# ICAN-7006-AiUi.net
KiCad netlist of a schematic drawn in Altium Designer
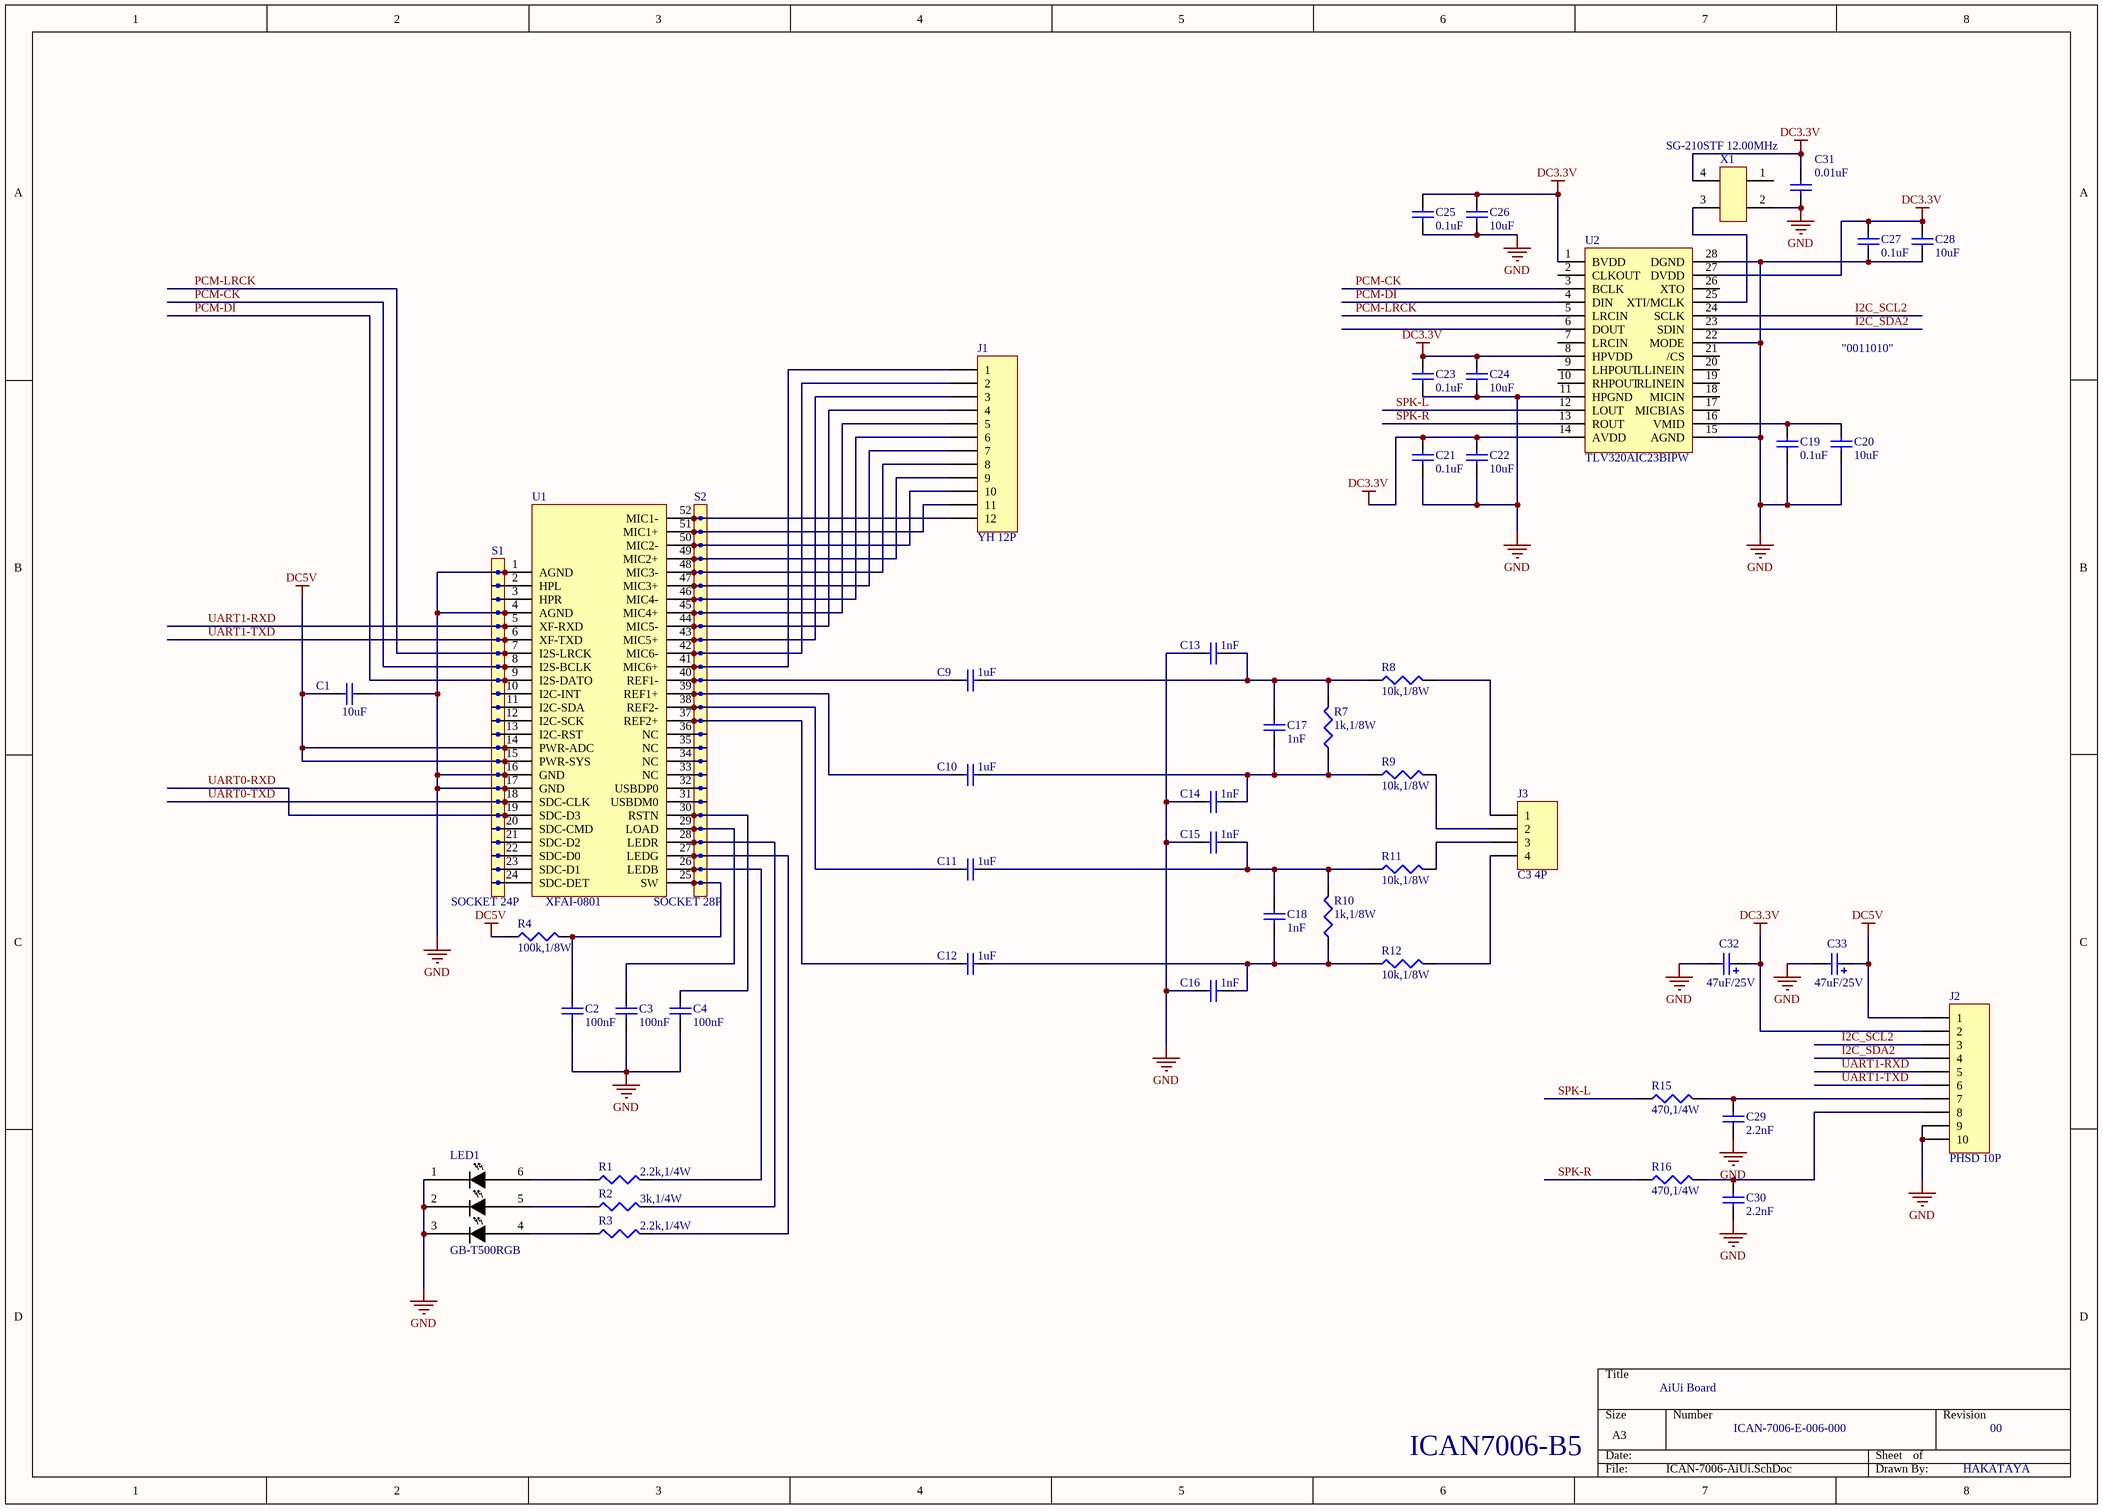
[diagram p0: ICAN-7006-AiUi.SchDoc]

(export (version "E")
  (design (tool "Eeschema 10.0.6"))
  (components
    (comp (ref "C1")
      (value "10uF")
      (footprint "[0805]2012")
      (description "Capacitor")
      (fields (field (name "PUBLISHER") "Altium Limited"))
      (libsource (lib "Miscellaneous Devices") (part "Cap Semi"))
    )
    (comp (ref "C2")
      (value "100nF")
      (footprint "[0805]2012")
      (description "Capacitor")
      (fields (field (name "PUBLISHER") "Altium Limited"))
      (libsource (lib "Miscellaneous Devices") (part "Cap Semi"))
    )
    (comp (ref "C3")
      (value "100nF")
      (footprint "[0805]2012")
      (description "Capacitor")
      (fields (field (name "PUBLISHER") "Altium Limited"))
      (libsource (lib "Miscellaneous Devices") (part "Cap Semi"))
    )
    (comp (ref "C4")
      (value "100nF")
      (footprint "[0805]2012")
      (description "Capacitor")
      (fields (field (name "PUBLISHER") "Altium Limited"))
      (libsource (lib "Miscellaneous Devices") (part "Cap Semi"))
    )
    (comp (ref "C9")
      (value "1uF")
      (footprint "[0805]2012")
      (description "Capacitor")
      (fields (field (name "PUBLISHER") "Altium Limited"))
      (libsource (lib "Miscellaneous Devices") (part "Cap Semi"))
    )
    (comp (ref "C10")
      (value "1uF")
      (footprint "[0805]2012")
      (description "Capacitor")
      (fields (field (name "PUBLISHER") "Altium Limited"))
      (libsource (lib "Miscellaneous Devices") (part "Cap Semi"))
    )
    (comp (ref "C11")
      (value "1uF")
      (footprint "[0805]2012")
      (description "Capacitor")
      (fields (field (name "PUBLISHER") "Altium Limited"))
      (libsource (lib "Miscellaneous Devices") (part "Cap Semi"))
    )
    (comp (ref "C12")
      (value "1uF")
      (footprint "[0805]2012")
      (description "Capacitor")
      (fields (field (name "PUBLISHER") "Altium Limited"))
      (libsource (lib "Miscellaneous Devices") (part "Cap Semi"))
    )
    (comp (ref "C13")
      (value "1nF")
      (footprint "[0805]2012")
      (description "Capacitor")
      (fields (field (name "PUBLISHER") "Altium Limited"))
      (libsource (lib "Miscellaneous Devices") (part "Cap Semi"))
    )
    (comp (ref "C14")
      (value "1nF")
      (footprint "[0805]2012")
      (description "Capacitor")
      (fields (field (name "PUBLISHER") "Altium Limited"))
      (libsource (lib "Miscellaneous Devices") (part "Cap Semi"))
    )
    (comp (ref "C15")
      (value "1nF")
      (footprint "[0805]2012")
      (description "Capacitor")
      (fields (field (name "PUBLISHER") "Altium Limited"))
      (libsource (lib "Miscellaneous Devices") (part "Cap Semi"))
    )
    (comp (ref "C16")
      (value "1nF")
      (footprint "[0805]2012")
      (description "Capacitor")
      (fields (field (name "PUBLISHER") "Altium Limited"))
      (libsource (lib "Miscellaneous Devices") (part "Cap Semi"))
    )
    (comp (ref "C17")
      (value "1nF")
      (footprint "[0805]2012")
      (description "Capacitor")
      (fields (field (name "PUBLISHER") "Altium Limited"))
      (libsource (lib "Miscellaneous Devices") (part "Cap Semi"))
    )
    (comp (ref "C18")
      (value "1nF")
      (footprint "[0805]2012")
      (description "Capacitor")
      (fields (field (name "PUBLISHER") "Altium Limited"))
      (libsource (lib "Miscellaneous Devices") (part "Cap Semi"))
    )
    (comp (ref "C19")
      (value "0.1uF")
      (footprint "[0805]2012")
      (description "Capacitor")
      (fields (field (name "PUBLISHER") "Altium Limited"))
      (libsource (lib "Miscellaneous Devices") (part "Cap Semi"))
    )
    (comp (ref "C20")
      (value "10uF")
      (footprint "[0805]2012")
      (description "Capacitor")
      (fields (field (name "PUBLISHER") "Altium Limited"))
      (libsource (lib "Miscellaneous Devices") (part "Cap Semi"))
    )
    (comp (ref "C21")
      (value "0.1uF")
      (footprint "[0805]2012")
      (description "Capacitor")
      (fields (field (name "PUBLISHER") "Altium Limited"))
      (libsource (lib "Miscellaneous Devices") (part "Cap Semi"))
    )
    (comp (ref "C22")
      (value "10uF")
      (footprint "[0805]2012")
      (description "Capacitor")
      (fields (field (name "PUBLISHER") "Altium Limited"))
      (libsource (lib "Miscellaneous Devices") (part "Cap Semi"))
    )
    (comp (ref "C23")
      (value "0.1uF")
      (footprint "[0805]2012")
      (description "Capacitor")
      (fields (field (name "PUBLISHER") "Altium Limited"))
      (libsource (lib "Miscellaneous Devices") (part "Cap Semi"))
    )
    (comp (ref "C24")
      (value "10uF")
      (footprint "[0805]2012")
      (description "Capacitor")
      (fields (field (name "PUBLISHER") "Altium Limited"))
      (libsource (lib "Miscellaneous Devices") (part "Cap Semi"))
    )
    (comp (ref "C25")
      (value "0.1uF")
      (footprint "[0805]2012")
      (description "Capacitor")
      (fields (field (name "PUBLISHER") "Altium Limited"))
      (libsource (lib "Miscellaneous Devices") (part "Cap Semi"))
    )
    (comp (ref "C26")
      (value "10uF")
      (footprint "[0805]2012")
      (description "Capacitor")
      (fields (field (name "PUBLISHER") "Altium Limited"))
      (libsource (lib "Miscellaneous Devices") (part "Cap Semi"))
    )
    (comp (ref "C27")
      (value "0.1uF")
      (footprint "[0805]2012")
      (description "Capacitor")
      (fields (field (name "PUBLISHER") "Altium Limited"))
      (libsource (lib "Miscellaneous Devices") (part "Cap Semi"))
    )
    (comp (ref "C28")
      (value "10uF")
      (footprint "[0805]2012")
      (description "Capacitor")
      (fields (field (name "PUBLISHER") "Altium Limited"))
      (libsource (lib "Miscellaneous Devices") (part "Cap Semi"))
    )
    (comp (ref "C29")
      (value "2.2nF")
      (footprint "[0805]2012")
      (description "Capacitor")
      (fields (field (name "PUBLISHER") "Altium Limited"))
      (libsource (lib "Miscellaneous Devices") (part "Cap Semi"))
    )
    (comp (ref "C30")
      (value "2.2nF")
      (footprint "[0805]2012")
      (description "Capacitor")
      (fields (field (name "PUBLISHER") "Altium Limited"))
      (libsource (lib "Miscellaneous Devices") (part "Cap Semi"))
    )
    (comp (ref "C31")
      (value "0.01uF")
      (footprint "HAKATAYA:[0805]2012")
      (description "Capacitor (Semiconductor SIM Model)")
      (fields (field (name "PUBLISHER") "Altium Limited"))
      (libsource (lib "Miscellaneous Devices") (part "Cap Semi"))
    )
    (comp (ref "C32")
      (value "47uF/25V")
      (footprint "HAKATAYA:Capa MH5 PITCH2.5mm")
      (description "Polarized Capacitor (Axial)")
      (fields (field (name "PUBLISHER") "Altium Limited"))
      (libsource (lib "Miscellaneous Devices") (part "Cap Pol2"))
    )
    (comp (ref "C33")
      (value "47uF/25V")
      (footprint "HAKATAYA:Capa MH5 PITCH2.5mm")
      (description "Polarized Capacitor (Axial)")
      (fields (field (name "PUBLISHER") "Altium Limited"))
      (libsource (lib "Miscellaneous Devices") (part "Cap Pol2"))
    )
    (comp (ref "J1")
      (value "YH 12P")
      (footprint "HAKATAYA:HY-12AW")
      (description "Header, 12-Pin")
      (fields (field (name "PUBLISHER") "Altium Limited"))
      (libsource (lib "Miscellaneous Connectors") (part "Header 12"))
    )
    (comp (ref "J2")
      (value "PHSD 10P")
      (footprint "HAKATAYA:PHSD WV05x2")
      (description "Header, 10-Pin")
      (fields (field (name "PUBLISHER") "Altium Limited"))
      (libsource (lib "Miscellaneous Connectors") (part "Header 10"))
    )
    (comp (ref "J3")
      (value "C3 4P")
      (footprint "HAKATAYA:C3-S4")
      (description "Header, 4-Pin")
      (fields (field (name "PUBLISHER") "Altium Limited"))
      (libsource (lib "Miscellaneous Connectors") (part "Header 4"))
    )
    (comp (ref "LED1")
      (value "GB-T500RGB")
      (footprint "HAKATAYA:LED SMD RGB")
      (description "LED RGB")
      (libsource (lib "*") (part "LED Tri-COLOR"))
    )
    (comp (ref "R1")
      (value "2.2k,1/4W")
      (footprint "[0805]2012")
      (description "Resistor")
      (fields (field (name "PUBLISHER") "Altium Limited"))
      (libsource (lib "Miscellaneous Devices") (part "Res3"))
    )
    (comp (ref "R2")
      (value "3k,1/4W")
      (footprint "[0805]2012")
      (description "Resistor")
      (fields (field (name "PUBLISHER") "Altium Limited"))
      (libsource (lib "Miscellaneous Devices") (part "Res3"))
    )
    (comp (ref "R3")
      (value "2.2k,1/4W")
      (footprint "[0805]2012")
      (description "Resistor")
      (fields (field (name "PUBLISHER") "Altium Limited"))
      (libsource (lib "Miscellaneous Devices") (part "Res3"))
    )
    (comp (ref "R4")
      (value "100k,1/8W")
      (footprint "[0805]2012")
      (description "Resistor")
      (fields (field (name "PUBLISHER") "Altium Limited"))
      (libsource (lib "Miscellaneous Devices") (part "Res3"))
    )
    (comp (ref "R7")
      (value "1k,1/8W")
      (footprint "[0805]2012")
      (description "Resistor")
      (fields (field (name "PUBLISHER") "Altium Limited"))
      (libsource (lib "Miscellaneous Devices") (part "Res3"))
    )
    (comp (ref "R8")
      (value "10k,1/8W")
      (footprint "[0805]2012")
      (description "Resistor")
      (fields (field (name "PUBLISHER") "Altium Limited"))
      (libsource (lib "Miscellaneous Devices") (part "Res3"))
    )
    (comp (ref "R9")
      (value "10k,1/8W")
      (footprint "[0805]2012")
      (description "Resistor")
      (fields (field (name "PUBLISHER") "Altium Limited"))
      (libsource (lib "Miscellaneous Devices") (part "Res3"))
    )
    (comp (ref "R10")
      (value "1k,1/8W")
      (footprint "[0805]2012")
      (description "Resistor")
      (fields (field (name "PUBLISHER") "Altium Limited"))
      (libsource (lib "Miscellaneous Devices") (part "Res3"))
    )
    (comp (ref "R11")
      (value "10k,1/8W")
      (footprint "[0805]2012")
      (description "Resistor")
      (fields (field (name "PUBLISHER") "Altium Limited"))
      (libsource (lib "Miscellaneous Devices") (part "Res3"))
    )
    (comp (ref "R12")
      (value "10k,1/8W")
      (footprint "[0805]2012")
      (description "Resistor")
      (fields (field (name "PUBLISHER") "Altium Limited"))
      (libsource (lib "Miscellaneous Devices") (part "Res3"))
    )
    (comp (ref "R15")
      (value "470,1/4W")
      (footprint "[0805]2012")
      (description "Resistor")
      (fields (field (name "PUBLISHER") "Altium Limited"))
      (libsource (lib "Miscellaneous Devices") (part "Res3"))
    )
    (comp (ref "R16")
      (value "470,1/4W")
      (footprint "[0805]2012")
      (description "Resistor")
      (fields (field (name "PUBLISHER") "Altium Limited"))
      (libsource (lib "Miscellaneous Devices") (part "Res3"))
    )
    (comp (ref "S1")
      (value "SOCKET 24P")
      (footprint "HAKATAYA:CONN 2.0mm X 24")
      (description "IC SOCKET")
      (libsource (lib "*") (part "SOCKET 24P"))
    )
    (comp (ref "S2")
      (value "SOCKET 28P")
      (footprint "HAKATAYA:CONN 2.0mm X 28")
      (description "IC SOCKET")
      (libsource (lib "*") (part "SOCKET 28P"))
    )
    (comp (ref "U1")
      (value "XFAI-0801")
      (footprint "HAKATAYA:XFAI-0801")
      (description "AiUI")
      (libsource (lib "HAKATAYA") (part "XFAI-0801"))
    )
    (comp (ref "U2")
      (value "TLV320AIC23BIPW")
      (footprint "HAKATAYA:PW 28p")
      (description "DAC")
      (libsource (lib "HAKATAYA") (part "IC28"))
    )
    (comp (ref "X1")
      (value "SG-210STF 12.00MHz")
      (footprint "HAKATAYA:XTAL SPXO")
      (description "Crystal oscilator")
      (libsource (lib "HAKATAYA") (part "IC4"))
    )
  )
  (nets
    (net (code "1") (name "/I2C_SCL2") (class "Default")
      (node (ref "J2") (pin "3") (pinfunction "3_3") (pintype "passive"))
      (node (ref "U2") (pin "24") (pinfunction "SCLK_24") (pintype "passive"))
    )
    (net (code "2") (name "/I2C_SDA2") (class "Default")
      (node (ref "J2") (pin "4") (pinfunction "4_4") (pintype "passive"))
      (node (ref "U2") (pin "23") (pinfunction "SDIN_23") (pintype "passive"))
    )
    (net (code "3") (name "/PCM-CK") (class "Default")
      (node (ref "S1") (pin "8") (pinfunction "8_8") (pintype "passive"))
      (node (ref "U1") (pin "8") (pinfunction "I2S-BCLK_8") (pintype "passive"))
      (node (ref "U2") (pin "3") (pinfunction "BCLK_3") (pintype "passive"))
    )
    (net (code "4") (name "/PCM-DI") (class "Default")
      (node (ref "S1") (pin "9") (pinfunction "9_9") (pintype "passive"))
      (node (ref "U1") (pin "9") (pinfunction "I2S-DATO_9") (pintype "passive"))
      (node (ref "U2") (pin "4") (pinfunction "DIN_4") (pintype "passive"))
    )
    (net (code "5") (name "/PCM-LRCK") (class "Default")
      (node (ref "S1") (pin "7") (pinfunction "7_7") (pintype "passive"))
      (node (ref "U1") (pin "7") (pinfunction "I2S-LRCK_7") (pintype "passive"))
      (node (ref "U2") (pin "5") (pinfunction "LRCIN_5") (pintype "passive"))
    )
    (net (code "6") (name "/SPK-L") (class "Default")
      (node (ref "R15") (pin "1") (pinfunction "1_1") (pintype "passive"))
      (node (ref "U2") (pin "12") (pinfunction "LOUT_12") (pintype "passive"))
    )
    (net (code "7") (name "/SPK-R") (class "Default")
      (node (ref "R16") (pin "1") (pinfunction "1_1") (pintype "passive"))
      (node (ref "U2") (pin "13") (pinfunction "ROUT_13") (pintype "passive"))
    )
    (net (code "8") (name "/UART0-RXD") (class "Default")
      (node (ref "S1") (pin "19") (pinfunction "19_19") (pintype "passive"))
      (node (ref "U1") (pin "19") (pinfunction "SDC-D3_19") (pintype "passive"))
    )
    (net (code "9") (name "/UART0-TXD") (class "Default")
      (node (ref "S1") (pin "18") (pinfunction "18_18") (pintype "passive"))
      (node (ref "U1") (pin "18") (pinfunction "SDC-CLK_18") (pintype "passive"))
    )
    (net (code "10") (name "/UART1-RXD") (class "Default")
      (node (ref "J2") (pin "5") (pinfunction "5_5") (pintype "passive"))
      (node (ref "S1") (pin "5") (pinfunction "5_5") (pintype "passive"))
      (node (ref "U1") (pin "5") (pinfunction "XF-RXD_5") (pintype "passive"))
    )
    (net (code "11") (name "/UART1-TXD") (class "Default")
      (node (ref "J2") (pin "6") (pinfunction "6_6") (pintype "passive"))
      (node (ref "S1") (pin "6") (pinfunction "6_6") (pintype "passive"))
      (node (ref "U1") (pin "6") (pinfunction "XF-TXD_6") (pintype "passive"))
    )
    (net (code "12") (name "DC3.3V") (class "Default")
      (node (ref "C21") (pin "2") (pinfunction "2_2") (pintype "passive"))
      (node (ref "C22") (pin "2") (pinfunction "2_2") (pintype "passive"))
      (node (ref "C23") (pin "2") (pinfunction "2_2") (pintype "passive"))
      (node (ref "C24") (pin "2") (pinfunction "2_2") (pintype "passive"))
      (node (ref "C25") (pin "2") (pinfunction "2_2") (pintype "passive"))
      (node (ref "C26") (pin "2") (pinfunction "2_2") (pintype "passive"))
      (node (ref "C27") (pin "2") (pinfunction "2_2") (pintype "passive"))
      (node (ref "C28") (pin "2") (pinfunction "2_2") (pintype "passive"))
      (node (ref "C31") (pin "2") (pinfunction "2_2") (pintype "passive"))
      (node (ref "C32") (pin "1") (pinfunction "1_1") (pintype "passive"))
      (node (ref "J2") (pin "2") (pinfunction "2_2") (pintype "passive"))
      (node (ref "U2") (pin "1") (pinfunction "BVDD_1") (pintype "passive"))
      (node (ref "U2") (pin "14") (pinfunction "AVDD_14") (pintype "passive"))
      (node (ref "U2") (pin "27") (pinfunction "DVDD_27") (pintype "passive"))
      (node (ref "U2") (pin "8") (pinfunction "HPVDD_8") (pintype "passive"))
      (node (ref "X1") (pin "4") (pinfunction "Vcc_4") (pintype "passive"))
    )
    (net (code "13") (name "DC5V") (class "Default")
      (node (ref "C1") (pin "1") (pinfunction "1_1") (pintype "passive"))
      (node (ref "C33") (pin "1") (pinfunction "1_1") (pintype "passive"))
      (node (ref "J2") (pin "1") (pinfunction "1_1") (pintype "passive"))
      (node (ref "R4") (pin "1") (pinfunction "1_1") (pintype "passive"))
      (node (ref "S1") (pin "14") (pinfunction "14_14") (pintype "passive"))
      (node (ref "S1") (pin "15") (pinfunction "15_15") (pintype "passive"))
      (node (ref "U1") (pin "14") (pinfunction "PWR-ADC_14") (pintype "passive"))
      (node (ref "U1") (pin "15") (pinfunction "PWR-SYS_15") (pintype "passive"))
    )
    (net (code "14") (name "GND") (class "Default")
      (node (ref "C1") (pin "2") (pinfunction "2_2") (pintype "passive"))
      (node (ref "C13") (pin "1") (pinfunction "1_1") (pintype "passive"))
      (node (ref "C14") (pin "1") (pinfunction "1_1") (pintype "passive"))
      (node (ref "C15") (pin "1") (pinfunction "1_1") (pintype "passive"))
      (node (ref "C16") (pin "1") (pinfunction "1_1") (pintype "passive"))
      (node (ref "C19") (pin "1") (pinfunction "1_1") (pintype "passive"))
      (node (ref "C2") (pin "1") (pinfunction "1_1") (pintype "passive"))
      (node (ref "C20") (pin "1") (pinfunction "1_1") (pintype "passive"))
      (node (ref "C21") (pin "1") (pinfunction "1_1") (pintype "passive"))
      (node (ref "C22") (pin "1") (pinfunction "1_1") (pintype "passive"))
      (node (ref "C23") (pin "1") (pinfunction "1_1") (pintype "passive"))
      (node (ref "C24") (pin "1") (pinfunction "1_1") (pintype "passive"))
      (node (ref "C25") (pin "1") (pinfunction "1_1") (pintype "passive"))
      (node (ref "C26") (pin "1") (pinfunction "1_1") (pintype "passive"))
      (node (ref "C27") (pin "1") (pinfunction "1_1") (pintype "passive"))
      (node (ref "C28") (pin "1") (pinfunction "1_1") (pintype "passive"))
      (node (ref "C29") (pin "1") (pinfunction "1_1") (pintype "passive"))
      (node (ref "C3") (pin "1") (pinfunction "1_1") (pintype "passive"))
      (node (ref "C30") (pin "1") (pinfunction "1_1") (pintype "passive"))
      (node (ref "C31") (pin "1") (pinfunction "1_1") (pintype "passive"))
      (node (ref "C32") (pin "2") (pinfunction "2_2") (pintype "passive"))
      (node (ref "C33") (pin "2") (pinfunction "2_2") (pintype "passive"))
      (node (ref "C4") (pin "1") (pinfunction "1_1") (pintype "passive"))
      (node (ref "J2") (pin "10") (pinfunction "10_10") (pintype "passive"))
      (node (ref "J2") (pin "9") (pinfunction "9_9") (pintype "passive"))
      (node (ref "LED1") (pin "1") (pinfunction "K1_1") (pintype "passive"))
      (node (ref "LED1") (pin "2") (pinfunction "K2_2") (pintype "passive"))
      (node (ref "LED1") (pin "3") (pinfunction "K3_3") (pintype "passive"))
      (node (ref "S1") (pin "1") (pinfunction "1_1") (pintype "passive"))
      (node (ref "S1") (pin "16") (pinfunction "16_16") (pintype "passive"))
      (node (ref "S1") (pin "17") (pinfunction "17_17") (pintype "passive"))
      (node (ref "S1") (pin "4") (pinfunction "4_4") (pintype "passive"))
      (node (ref "U1") (pin "1") (pinfunction "AGND_1") (pintype "passive"))
      (node (ref "U1") (pin "16") (pinfunction "GND_16") (pintype "passive"))
      (node (ref "U1") (pin "17") (pinfunction "GND_17") (pintype "passive"))
      (node (ref "U1") (pin "4") (pinfunction "AGND_4") (pintype "passive"))
      (node (ref "U2") (pin "11") (pinfunction "HPGND_11") (pintype "passive"))
      (node (ref "U2") (pin "15") (pinfunction "AGND_15") (pintype "passive"))
      (node (ref "U2") (pin "22") (pinfunction "MODE_22") (pintype "passive"))
      (node (ref "U2") (pin "28") (pinfunction "DGND_28") (pintype "passive"))
      (node (ref "X1") (pin "2") (pinfunction "GND_2") (pintype "passive"))
    )
    (net (code "15") (name "Net-(C10-Pad2)") (class "Default")
      (node (ref "C10") (pin "2") (pinfunction "2_2") (pintype "passive"))
      (node (ref "C14") (pin "2") (pinfunction "2_2") (pintype "passive"))
      (node (ref "C17") (pin "1") (pinfunction "1_1") (pintype "passive"))
      (node (ref "R7") (pin "1") (pinfunction "1_1") (pintype "passive"))
      (node (ref "R9") (pin "1") (pinfunction "1_1") (pintype "passive"))
    )
    (net (code "16") (name "Net-(C11-Pad2)") (class "Default")
      (node (ref "C11") (pin "2") (pinfunction "2_2") (pintype "passive"))
      (node (ref "C15") (pin "2") (pinfunction "2_2") (pintype "passive"))
      (node (ref "C18") (pin "2") (pinfunction "2_2") (pintype "passive"))
      (node (ref "R10") (pin "2") (pinfunction "2_2") (pintype "passive"))
      (node (ref "R11") (pin "1") (pinfunction "1_1") (pintype "passive"))
    )
    (net (code "17") (name "Net-(C12-Pad2)") (class "Default")
      (node (ref "C12") (pin "2") (pinfunction "2_2") (pintype "passive"))
      (node (ref "C16") (pin "2") (pinfunction "2_2") (pintype "passive"))
      (node (ref "C18") (pin "1") (pinfunction "1_1") (pintype "passive"))
      (node (ref "R10") (pin "1") (pinfunction "1_1") (pintype "passive"))
      (node (ref "R12") (pin "1") (pinfunction "1_1") (pintype "passive"))
    )
    (net (code "18") (name "Net-(C13-Pad2)") (class "Default")
      (node (ref "C13") (pin "2") (pinfunction "2_2") (pintype "passive"))
      (node (ref "C17") (pin "2") (pinfunction "2_2") (pintype "passive"))
      (node (ref "C9") (pin "2") (pinfunction "2_2") (pintype "passive"))
      (node (ref "R7") (pin "2") (pinfunction "2_2") (pintype "passive"))
      (node (ref "R8") (pin "1") (pinfunction "1_1") (pintype "passive"))
    )
    (net (code "19") (name "Net-(C29-Pad2)") (class "Default")
      (node (ref "C29") (pin "2") (pinfunction "2_2") (pintype "passive"))
      (node (ref "J2") (pin "7") (pinfunction "7_7") (pintype "passive"))
      (node (ref "R15") (pin "2") (pinfunction "2_2") (pintype "passive"))
    )
    (net (code "20") (name "Net-(C30-Pad2)") (class "Default")
      (node (ref "C30") (pin "2") (pinfunction "2_2") (pintype "passive"))
      (node (ref "J2") (pin "8") (pinfunction "8_8") (pintype "passive"))
      (node (ref "R16") (pin "2") (pinfunction "2_2") (pintype "passive"))
    )
    (net (code "21") (name "Net-(J3-Pad1)") (class "Default")
      (node (ref "J3") (pin "1") (pinfunction "1_1") (pintype "passive"))
      (node (ref "R8") (pin "2") (pinfunction "2_2") (pintype "passive"))
    )
    (net (code "22") (name "Net-(J3-Pad2)") (class "Default")
      (node (ref "J3") (pin "2") (pinfunction "2_2") (pintype "passive"))
      (node (ref "R9") (pin "2") (pinfunction "2_2") (pintype "passive"))
    )
    (net (code "23") (name "Net-(J3-Pad3)") (class "Default")
      (node (ref "J3") (pin "3") (pinfunction "3_3") (pintype "passive"))
      (node (ref "R11") (pin "2") (pinfunction "2_2") (pintype "passive"))
    )
    (net (code "24") (name "Net-(J3-Pad4)") (class "Default")
      (node (ref "J3") (pin "4") (pinfunction "4_4") (pintype "passive"))
      (node (ref "R12") (pin "2") (pinfunction "2_2") (pintype "passive"))
    )
    (net (code "25") (name "Net-(LED1-A1)") (class "Default")
      (node (ref "LED1") (pin "6") (pinfunction "A1_6") (pintype "passive"))
      (node (ref "R1") (pin "1") (pinfunction "1_1") (pintype "passive"))
    )
    (net (code "26") (name "Net-(LED1-A2)") (class "Default")
      (node (ref "LED1") (pin "5") (pinfunction "A2_5") (pintype "passive"))
      (node (ref "R2") (pin "1") (pinfunction "1_1") (pintype "passive"))
    )
    (net (code "27") (name "Net-(LED1-A3)") (class "Default")
      (node (ref "LED1") (pin "4") (pinfunction "A3_4") (pintype "passive"))
      (node (ref "R3") (pin "1") (pinfunction "1_1") (pintype "passive"))
    )
    (net (code "28") (name "Net-(S2-Pad17)") (class "Default")
      (node (ref "S2") (pin "17") (pinfunction "17_17") (pintype "passive"))
      (node (ref "U1") (pin "36") (pinfunction "NC_36") (pintype "passive"))
    )
    (net (code "29") (name "Net-(S2-Pad18)") (class "Default")
      (node (ref "S2") (pin "18") (pinfunction "18_18") (pintype "passive"))
      (node (ref "U1") (pin "35") (pinfunction "NC_35") (pintype "passive"))
    )
    (net (code "30") (name "Net-(S2-Pad19)") (class "Default")
      (node (ref "S2") (pin "19") (pinfunction "19_19") (pintype "passive"))
      (node (ref "U1") (pin "34") (pinfunction "NC_34") (pintype "passive"))
    )
    (net (code "31") (name "Net-(S2-Pad20)") (class "Default")
      (node (ref "S2") (pin "20") (pinfunction "20_20") (pintype "passive"))
      (node (ref "U1") (pin "33") (pinfunction "NC_33") (pintype "passive"))
    )
    (net (code "32") (name "Net-(U1-HPL)") (class "Default")
      (node (ref "S1") (pin "2") (pinfunction "2_2") (pintype "passive"))
      (node (ref "U1") (pin "2") (pinfunction "HPL_2") (pintype "passive"))
    )
    (net (code "33") (name "Net-(U1-HPR)") (class "Default")
      (node (ref "S1") (pin "3") (pinfunction "3_3") (pintype "passive"))
      (node (ref "U1") (pin "3") (pinfunction "HPR_3") (pintype "passive"))
    )
    (net (code "34") (name "Net-(U1-I2C-INT)") (class "Default")
      (node (ref "S1") (pin "10") (pinfunction "10_10") (pintype "passive"))
      (node (ref "U1") (pin "10") (pinfunction "I2C-INT_10") (pintype "passive"))
    )
    (net (code "35") (name "Net-(U1-I2C-RST)") (class "Default")
      (node (ref "S1") (pin "13") (pinfunction "13_13") (pintype "passive"))
      (node (ref "U1") (pin "13") (pinfunction "I2C-RST_13") (pintype "passive"))
    )
    (net (code "36") (name "Net-(U1-I2C-SCK)") (class "Default")
      (node (ref "S1") (pin "12") (pinfunction "12_12") (pintype "passive"))
      (node (ref "U1") (pin "12") (pinfunction "I2C-SCK_12") (pintype "passive"))
    )
    (net (code "37") (name "Net-(U1-I2C-SDA)") (class "Default")
      (node (ref "S1") (pin "11") (pinfunction "11_11") (pintype "passive"))
      (node (ref "U1") (pin "11") (pinfunction "I2C-SDA_11") (pintype "passive"))
    )
    (net (code "38") (name "Net-(U1-LEDB)") (class "Default")
      (node (ref "R1") (pin "2") (pinfunction "2_2") (pintype "passive"))
      (node (ref "S2") (pin "27") (pinfunction "27_27") (pintype "passive"))
      (node (ref "U1") (pin "26") (pinfunction "LEDB_26") (pintype "passive"))
    )
    (net (code "39") (name "Net-(U1-LEDG)") (class "Default")
      (node (ref "R3") (pin "2") (pinfunction "2_2") (pintype "passive"))
      (node (ref "S2") (pin "26") (pinfunction "26_26") (pintype "passive"))
      (node (ref "U1") (pin "27") (pinfunction "LEDG_27") (pintype "passive"))
    )
    (net (code "40") (name "Net-(U1-LEDR)") (class "Default")
      (node (ref "R2") (pin "2") (pinfunction "2_2") (pintype "passive"))
      (node (ref "S2") (pin "25") (pinfunction "25_25") (pintype "passive"))
      (node (ref "U1") (pin "28") (pinfunction "LEDR_28") (pintype "passive"))
    )
    (net (code "41") (name "Net-(U1-LOAD)") (class "Default")
      (node (ref "C3") (pin "2") (pinfunction "2_2") (pintype "passive"))
      (node (ref "S2") (pin "24") (pinfunction "24_24") (pintype "passive"))
      (node (ref "U1") (pin "29") (pinfunction "LOAD_29") (pintype "passive"))
    )
    (net (code "42") (name "Net-(U1-MIC1+)") (class "Default")
      (node (ref "J1") (pin "11") (pinfunction "11_11") (pintype "passive"))
      (node (ref "S2") (pin "2") (pinfunction "2_2") (pintype "passive"))
      (node (ref "U1") (pin "51") (pinfunction "MIC1+_51") (pintype "passive"))
    )
    (net (code "43") (name "Net-(U1-MIC1-)") (class "Default")
      (node (ref "J1") (pin "12") (pinfunction "12_12") (pintype "passive"))
      (node (ref "S2") (pin "1") (pinfunction "1_1") (pintype "passive"))
      (node (ref "U1") (pin "52") (pinfunction "MIC1-_52") (pintype "passive"))
    )
    (net (code "44") (name "Net-(U1-MIC2+)") (class "Default")
      (node (ref "J1") (pin "9") (pinfunction "9_9") (pintype "passive"))
      (node (ref "S2") (pin "4") (pinfunction "4_4") (pintype "passive"))
      (node (ref "U1") (pin "49") (pinfunction "MIC2+_49") (pintype "passive"))
    )
    (net (code "45") (name "Net-(U1-MIC2-)") (class "Default")
      (node (ref "J1") (pin "10") (pinfunction "10_10") (pintype "passive"))
      (node (ref "S2") (pin "3") (pinfunction "3_3") (pintype "passive"))
      (node (ref "U1") (pin "50") (pinfunction "MIC2-_50") (pintype "passive"))
    )
    (net (code "46") (name "Net-(U1-MIC3+)") (class "Default")
      (node (ref "J1") (pin "7") (pinfunction "7_7") (pintype "passive"))
      (node (ref "S2") (pin "6") (pinfunction "6_6") (pintype "passive"))
      (node (ref "U1") (pin "47") (pinfunction "MIC3+_47") (pintype "passive"))
    )
    (net (code "47") (name "Net-(U1-MIC3-)") (class "Default")
      (node (ref "J1") (pin "8") (pinfunction "8_8") (pintype "passive"))
      (node (ref "S2") (pin "5") (pinfunction "5_5") (pintype "passive"))
      (node (ref "U1") (pin "48") (pinfunction "MIC3-_48") (pintype "passive"))
    )
    (net (code "48") (name "Net-(U1-MIC4+)") (class "Default")
      (node (ref "J1") (pin "5") (pinfunction "5_5") (pintype "passive"))
      (node (ref "S2") (pin "8") (pinfunction "8_8") (pintype "passive"))
      (node (ref "U1") (pin "45") (pinfunction "MIC4+_45") (pintype "passive"))
    )
    (net (code "49") (name "Net-(U1-MIC4-)") (class "Default")
      (node (ref "J1") (pin "6") (pinfunction "6_6") (pintype "passive"))
      (node (ref "S2") (pin "7") (pinfunction "7_7") (pintype "passive"))
      (node (ref "U1") (pin "46") (pinfunction "MIC4-_46") (pintype "passive"))
    )
    (net (code "50") (name "Net-(U1-MIC5+)") (class "Default")
      (node (ref "J1") (pin "3") (pinfunction "3_3") (pintype "passive"))
      (node (ref "S2") (pin "10") (pinfunction "10_10") (pintype "passive"))
      (node (ref "U1") (pin "43") (pinfunction "MIC5+_43") (pintype "passive"))
    )
    (net (code "51") (name "Net-(U1-MIC5-)") (class "Default")
      (node (ref "J1") (pin "4") (pinfunction "4_4") (pintype "passive"))
      (node (ref "S2") (pin "9") (pinfunction "9_9") (pintype "passive"))
      (node (ref "U1") (pin "44") (pinfunction "MIC5-_44") (pintype "passive"))
    )
    (net (code "52") (name "Net-(U1-MIC6+)") (class "Default")
      (node (ref "J1") (pin "1") (pinfunction "1_1") (pintype "passive"))
      (node (ref "S2") (pin "12") (pinfunction "12_12") (pintype "passive"))
      (node (ref "U1") (pin "41") (pinfunction "MIC6+_41") (pintype "passive"))
    )
    (net (code "53") (name "Net-(U1-MIC6-)") (class "Default")
      (node (ref "J1") (pin "2") (pinfunction "2_2") (pintype "passive"))
      (node (ref "S2") (pin "11") (pinfunction "11_11") (pintype "passive"))
      (node (ref "U1") (pin "42") (pinfunction "MIC6-_42") (pintype "passive"))
    )
    (net (code "54") (name "Net-(U1-REF1+)") (class "Default")
      (node (ref "C10") (pin "1") (pinfunction "1_1") (pintype "passive"))
      (node (ref "S2") (pin "14") (pinfunction "14_14") (pintype "passive"))
      (node (ref "U1") (pin "39") (pinfunction "REF1+_39") (pintype "passive"))
    )
    (net (code "55") (name "Net-(U1-REF1-)") (class "Default")
      (node (ref "C9") (pin "1") (pinfunction "1_1") (pintype "passive"))
      (node (ref "S2") (pin "13") (pinfunction "13_13") (pintype "passive"))
      (node (ref "U1") (pin "40") (pinfunction "REF1-_40") (pintype "passive"))
    )
    (net (code "56") (name "Net-(U1-REF2+)") (class "Default")
      (node (ref "C12") (pin "1") (pinfunction "1_1") (pintype "passive"))
      (node (ref "S2") (pin "16") (pinfunction "16_16") (pintype "passive"))
      (node (ref "U1") (pin "37") (pinfunction "REF2+_37") (pintype "passive"))
    )
    (net (code "57") (name "Net-(U1-REF2-)") (class "Default")
      (node (ref "C11") (pin "1") (pinfunction "1_1") (pintype "passive"))
      (node (ref "S2") (pin "15") (pinfunction "15_15") (pintype "passive"))
      (node (ref "U1") (pin "38") (pinfunction "REF2-_38") (pintype "passive"))
    )
    (net (code "58") (name "Net-(U1-RSTN)") (class "Default")
      (node (ref "C4") (pin "2") (pinfunction "2_2") (pintype "passive"))
      (node (ref "S2") (pin "23") (pinfunction "23_23") (pintype "passive"))
      (node (ref "U1") (pin "30") (pinfunction "RSTN_30") (pintype "passive"))
    )
    (net (code "59") (name "Net-(U1-SDC-CMD)") (class "Default")
      (node (ref "S1") (pin "20") (pinfunction "20_20") (pintype "passive"))
      (node (ref "U1") (pin "20") (pinfunction "SDC-CMD_20") (pintype "passive"))
    )
    (net (code "60") (name "Net-(U1-SDC-D0)") (class "Default")
      (node (ref "S1") (pin "22") (pinfunction "22_22") (pintype "passive"))
      (node (ref "U1") (pin "22") (pinfunction "SDC-D0_22") (pintype "passive"))
    )
    (net (code "61") (name "Net-(U1-SDC-D1)") (class "Default")
      (node (ref "S1") (pin "23") (pinfunction "23_23") (pintype "passive"))
      (node (ref "U1") (pin "23") (pinfunction "SDC-D1_23") (pintype "passive"))
    )
    (net (code "62") (name "Net-(U1-SDC-D2)") (class "Default")
      (node (ref "S1") (pin "21") (pinfunction "21_21") (pintype "passive"))
      (node (ref "U1") (pin "21") (pinfunction "SDC-D2_21") (pintype "passive"))
    )
    (net (code "63") (name "Net-(U1-SDC-DET)") (class "Default")
      (node (ref "S1") (pin "24") (pinfunction "24_24") (pintype "passive"))
      (node (ref "U1") (pin "24") (pinfunction "SDC-DET_24") (pintype "passive"))
    )
    (net (code "64") (name "Net-(U1-SW)") (class "Default")
      (node (ref "C2") (pin "2") (pinfunction "2_2") (pintype "passive"))
      (node (ref "R4") (pin "2") (pinfunction "2_2") (pintype "passive"))
      (node (ref "S2") (pin "28") (pinfunction "28_28") (pintype "passive"))
      (node (ref "U1") (pin "25") (pinfunction "SW_25") (pintype "passive"))
    )
    (net (code "65") (name "Net-(U1-USBDM0)") (class "Default")
      (node (ref "S2") (pin "22") (pinfunction "22_22") (pintype "passive"))
      (node (ref "U1") (pin "31") (pinfunction "USBDM0_31") (pintype "passive"))
    )
    (net (code "66") (name "Net-(U1-USBDP0)") (class "Default")
      (node (ref "S2") (pin "21") (pinfunction "21_21") (pintype "passive"))
      (node (ref "U1") (pin "32") (pinfunction "USBDP0_32") (pintype "passive"))
    )
    (net (code "67") (name "Net-(U2-VMID)") (class "Default")
      (node (ref "C19") (pin "2") (pinfunction "2_2") (pintype "passive"))
      (node (ref "C20") (pin "2") (pinfunction "2_2") (pintype "passive"))
      (node (ref "U2") (pin "16") (pinfunction "VMID_16") (pintype "passive"))
    )
    (net (code "68") (name "Net-(U2-XTI{slash}MCLK)") (class "Default")
      (node (ref "U2") (pin "25") (pinfunction "XTI/MCLK_25") (pintype "passive"))
      (node (ref "X1") (pin "3") (pinfunction "OUT_3") (pintype "passive"))
    )
    (net (code "69") (name "unconnected-(U2-CLKOUT-Pad2)") (class "Default")
      (node (ref "U2") (pin "2") (pinfunction "CLKOUT_2") (pintype "passive"))
    )
    (net (code "70") (name "unconnected-(U2-DOUT-Pad6)") (class "Default")
      (node (ref "U2") (pin "6") (pinfunction "DOUT_6") (pintype "passive"))
    )
    (net (code "71") (name "unconnected-(U2-LHPOUT-Pad9)") (class "Default")
      (node (ref "U2") (pin "9") (pinfunction "LHPOUT_9") (pintype "passive"))
    )
    (net (code "72") (name "unconnected-(U2-LLINEIN-Pad20)") (class "Default")
      (node (ref "U2") (pin "20") (pinfunction "LLINEIN_20") (pintype "passive"))
    )
    (net (code "73") (name "unconnected-(U2-LRCIN-Pad7)") (class "Default")
      (node (ref "U2") (pin "7") (pinfunction "LRCIN_7") (pintype "passive"))
    )
    (net (code "74") (name "unconnected-(U2-MICBIAS-Pad17)") (class "Default")
      (node (ref "U2") (pin "17") (pinfunction "MICBIAS_17") (pintype "passive"))
    )
    (net (code "75") (name "unconnected-(U2-MICIN-Pad18)") (class "Default")
      (node (ref "U2") (pin "18") (pinfunction "MICIN_18") (pintype "passive"))
    )
    (net (code "76") (name "unconnected-(U2-RHPOUT-Pad10)") (class "Default")
      (node (ref "U2") (pin "10") (pinfunction "RHPOUT_10") (pintype "passive"))
    )
    (net (code "77") (name "unconnected-(U2-RLINEIN-Pad19)") (class "Default")
      (node (ref "U2") (pin "19") (pinfunction "RLINEIN_19") (pintype "passive"))
    )
    (net (code "78") (name "unconnected-(U2-XTO-Pad26)") (class "Default")
      (node (ref "U2") (pin "26") (pinfunction "XTO_26") (pintype "passive"))
    )
    (net (code "79") (name "unconnected-(U2-{slash}CS-Pad21)") (class "Default")
      (node (ref "U2") (pin "21") (pinfunction "/CS_21") (pintype "passive"))
    )
    (net (code "80") (name "unconnected-(X1-*ST-Pad1)") (class "Default")
      (node (ref "X1") (pin "1") (pinfunction "*ST_1") (pintype "passive"))
    )
  )
)
